# ADS7828-TSSOP.net
KiCad netlist of a schematic drawn in EAGLE
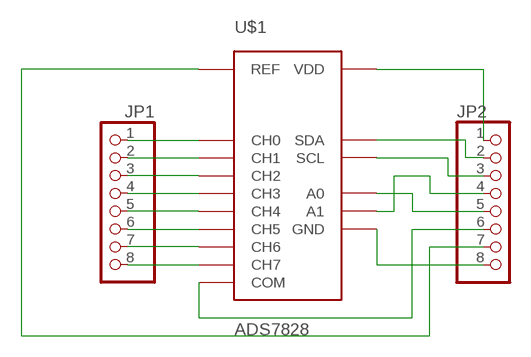
[diagram p0: schematic, sheet 1]

(export (version "E")
  (design (tool "Eeschema 10.0.6"))
  (components
    (comp (ref "JP1")
      (value "PINHD-1X8")
      (footprint "eagle-import:1X08")
      (libsource (lib "eagle-import") (part "PINHD-1X8"))
    )
    (comp (ref "JP2")
      (value "PINHD-1X8")
      (footprint "eagle-import:1X08")
      (libsource (lib "eagle-import") (part "PINHD-1X8"))
    )
    (comp (ref "U$1")
      (value "ADS7828")
      (footprint "eagle-import:TSSOP16")
      (libsource (lib "eagle-import") (part "ADS7828"))
    )
  )
  (nets
    (net (code "1") (name "Net-(U$1-A0)") (class "Default")
      (node (ref "JP2") (pin "5") (pinfunction "5_5") (pintype "passive"))
      (node (ref "U$1") (pin "12") (pinfunction "A0_12") (pintype "bidirectional"))
    )
    (net (code "2") (name "Net-(U$1-A1)") (class "Default")
      (node (ref "JP2") (pin "4") (pinfunction "4_4") (pintype "passive"))
      (node (ref "U$1") (pin "13") (pinfunction "A1_13") (pintype "bidirectional"))
    )
    (net (code "3") (name "Net-(U$1-CH0)") (class "Default")
      (node (ref "JP1") (pin "1") (pinfunction "1_1") (pintype "passive"))
      (node (ref "U$1") (pin "1") (pinfunction "CH0_1") (pintype "bidirectional"))
    )
    (net (code "4") (name "Net-(U$1-CH1)") (class "Default")
      (node (ref "JP1") (pin "2") (pinfunction "2_2") (pintype "passive"))
      (node (ref "U$1") (pin "2") (pinfunction "CH1_2") (pintype "bidirectional"))
    )
    (net (code "5") (name "Net-(U$1-CH2)") (class "Default")
      (node (ref "JP1") (pin "3") (pinfunction "3_3") (pintype "passive"))
      (node (ref "U$1") (pin "3") (pinfunction "CH2_3") (pintype "bidirectional"))
    )
    (net (code "6") (name "Net-(U$1-CH3)") (class "Default")
      (node (ref "JP1") (pin "4") (pinfunction "4_4") (pintype "passive"))
      (node (ref "U$1") (pin "4") (pinfunction "CH3_4") (pintype "bidirectional"))
    )
    (net (code "7") (name "Net-(U$1-CH4)") (class "Default")
      (node (ref "JP1") (pin "5") (pinfunction "5_5") (pintype "passive"))
      (node (ref "U$1") (pin "5") (pinfunction "CH4_5") (pintype "bidirectional"))
    )
    (net (code "8") (name "Net-(U$1-CH5)") (class "Default")
      (node (ref "JP1") (pin "6") (pinfunction "6_6") (pintype "passive"))
      (node (ref "U$1") (pin "6") (pinfunction "CH5_6") (pintype "bidirectional"))
    )
    (net (code "9") (name "Net-(U$1-CH6)") (class "Default")
      (node (ref "JP1") (pin "7") (pinfunction "7_7") (pintype "passive"))
      (node (ref "U$1") (pin "7") (pinfunction "CH6_7") (pintype "bidirectional"))
    )
    (net (code "10") (name "Net-(U$1-CH7)") (class "Default")
      (node (ref "JP1") (pin "8") (pinfunction "8_8") (pintype "passive"))
      (node (ref "U$1") (pin "8") (pinfunction "CH7_8") (pintype "bidirectional"))
    )
    (net (code "11") (name "Net-(U$1-COM)") (class "Default")
      (node (ref "JP2") (pin "6") (pinfunction "6_6") (pintype "passive"))
      (node (ref "U$1") (pin "11") (pinfunction "COM_11") (pintype "bidirectional"))
    )
    (net (code "12") (name "Net-(U$1-GND)") (class "Default")
      (node (ref "JP2") (pin "8") (pinfunction "8_8") (pintype "passive"))
      (node (ref "U$1") (pin "9") (pinfunction "GND_9") (pintype "bidirectional"))
    )
    (net (code "13") (name "Net-(U$1-REF)") (class "Default")
      (node (ref "JP2") (pin "7") (pinfunction "7_7") (pintype "passive"))
      (node (ref "U$1") (pin "10") (pinfunction "REF_10") (pintype "bidirectional"))
    )
    (net (code "14") (name "Net-(U$1-SCL)") (class "Default")
      (node (ref "JP2") (pin "3") (pinfunction "3_3") (pintype "passive"))
      (node (ref "U$1") (pin "14") (pinfunction "SCL_14") (pintype "bidirectional"))
    )
    (net (code "15") (name "Net-(U$1-SDA)") (class "Default")
      (node (ref "JP2") (pin "2") (pinfunction "2_2") (pintype "passive"))
      (node (ref "U$1") (pin "15") (pinfunction "SDA_15") (pintype "bidirectional"))
    )
    (net (code "16") (name "Net-(U$1-VDD)") (class "Default")
      (node (ref "JP2") (pin "1") (pinfunction "1_1") (pintype "passive"))
      (node (ref "U$1") (pin "16") (pinfunction "VDD_16") (pintype "bidirectional"))
    )
  )
)
